# CRUVI-GT.net
KiCad netlist of a schematic drawn in Altium Designer
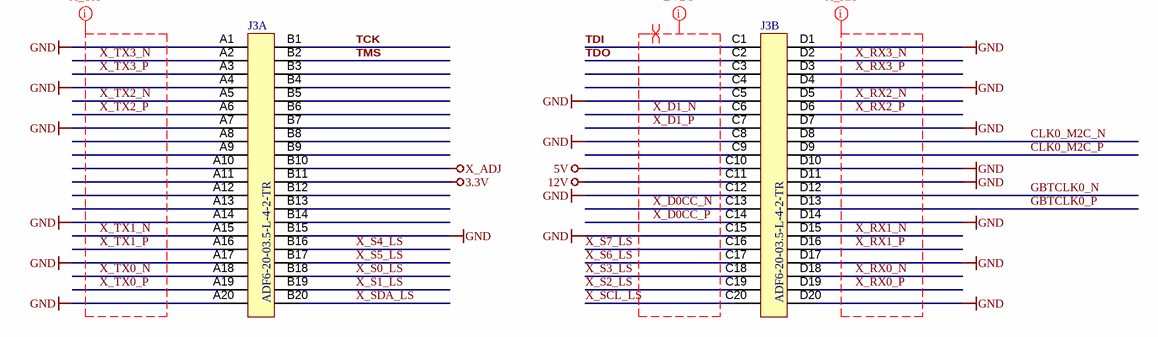
[diagram p0: CRUVI-GT.SchDoc]

(export (version "E")
  (design (tool "Eeschema 10.0.6"))
  (components
    (comp (ref "J3")
      (value "ADF6-20-03.5-L-4-2-TR")
      (footprint "ADF6-20-03.5-L-4-2")
      (fields (field (name "VOLTAGE") "155 VAC"))
      (libsource (lib "TE") (part "CON-20-A-D"))
    )
  )
  (nets
    (net (code "1") (name "/CLK0_M2C_N") (class "Default")
      (node (ref "J3") (pin "D8") (pinfunction "D8_D8") (pintype "passive"))
    )
    (net (code "2") (name "/CLK0_M2C_P") (class "Default")
      (node (ref "J3") (pin "D9") (pinfunction "D9_D9") (pintype "passive"))
    )
    (net (code "3") (name "/GBTCLK0_N") (class "Default")
      (node (ref "J3") (pin "D12") (pinfunction "D12_D12") (pintype "passive"))
    )
    (net (code "4") (name "/GBTCLK0_P") (class "Default")
      (node (ref "J3") (pin "D13") (pinfunction "D13_D13") (pintype "passive"))
    )
    (net (code "5") (name "/TCK") (class "Default")
      (node (ref "J3") (pin "B1") (pinfunction "B1_B1") (pintype "passive"))
    )
    (net (code "6") (name "/TDI") (class "Default")
      (node (ref "J3") (pin "C1") (pinfunction "C1_C1") (pintype "passive"))
    )
    (net (code "7") (name "/TDO") (class "Default")
      (node (ref "J3") (pin "C2") (pinfunction "C2_C2") (pintype "passive"))
    )
    (net (code "8") (name "/TMS") (class "Default")
      (node (ref "J3") (pin "B2") (pinfunction "B2_B2") (pintype "passive"))
    )
    (net (code "9") (name "/X_D0CC_N") (class "Default")
      (node (ref "J3") (pin "C13") (pinfunction "C13_C13") (pintype "passive"))
    )
    (net (code "10") (name "/X_D0CC_P") (class "Default")
      (node (ref "J3") (pin "C14") (pinfunction "C14_C14") (pintype "passive"))
    )
    (net (code "11") (name "/X_D1_N") (class "Default")
      (node (ref "J3") (pin "C6") (pinfunction "C6_C6") (pintype "passive"))
    )
    (net (code "12") (name "/X_D1_P") (class "Default")
      (node (ref "J3") (pin "C7") (pinfunction "C7_C7") (pintype "passive"))
    )
    (net (code "13") (name "/X_RX0_N") (class "Default")
      (node (ref "J3") (pin "D18") (pinfunction "D18_D18") (pintype "passive"))
    )
    (net (code "14") (name "/X_RX0_P") (class "Default")
      (node (ref "J3") (pin "D19") (pinfunction "D19_D19") (pintype "passive"))
    )
    (net (code "15") (name "/X_RX1_N") (class "Default")
      (node (ref "J3") (pin "D15") (pinfunction "D15_D15") (pintype "passive"))
    )
    (net (code "16") (name "/X_RX1_P") (class "Default")
      (node (ref "J3") (pin "D16") (pinfunction "D16_D16") (pintype "passive"))
    )
    (net (code "17") (name "/X_RX2_N") (class "Default")
      (node (ref "J3") (pin "D5") (pinfunction "D5_D5") (pintype "passive"))
    )
    (net (code "18") (name "/X_RX2_P") (class "Default")
      (node (ref "J3") (pin "D6") (pinfunction "D6_D6") (pintype "passive"))
    )
    (net (code "19") (name "/X_RX3_N") (class "Default")
      (node (ref "J3") (pin "D2") (pinfunction "D2_D2") (pintype "passive"))
    )
    (net (code "20") (name "/X_RX3_P") (class "Default")
      (node (ref "J3") (pin "D3") (pinfunction "D3_D3") (pintype "passive"))
    )
    (net (code "21") (name "/X_S0_LS") (class "Default")
      (node (ref "J3") (pin "B18") (pinfunction "B18_B18") (pintype "passive"))
    )
    (net (code "22") (name "/X_S1_LS") (class "Default")
      (node (ref "J3") (pin "B19") (pinfunction "B19_B19") (pintype "passive"))
    )
    (net (code "23") (name "/X_S2_LS") (class "Default")
      (node (ref "J3") (pin "C19") (pinfunction "C19_C19") (pintype "passive"))
    )
    (net (code "24") (name "/X_S3_LS") (class "Default")
      (node (ref "J3") (pin "C18") (pinfunction "C18_C18") (pintype "passive"))
    )
    (net (code "25") (name "/X_S4_LS") (class "Default")
      (node (ref "J3") (pin "B16") (pinfunction "B16_B16") (pintype "passive"))
    )
    (net (code "26") (name "/X_S5_LS") (class "Default")
      (node (ref "J3") (pin "B17") (pinfunction "B17_B17") (pintype "passive"))
    )
    (net (code "27") (name "/X_S6_LS") (class "Default")
      (node (ref "J3") (pin "C17") (pinfunction "C17_C17") (pintype "passive"))
    )
    (net (code "28") (name "/X_S7_LS") (class "Default")
      (node (ref "J3") (pin "C16") (pinfunction "C16_C16") (pintype "passive"))
    )
    (net (code "29") (name "/X_SCL_LS") (class "Default")
      (node (ref "J3") (pin "C20") (pinfunction "C20_C20") (pintype "passive"))
    )
    (net (code "30") (name "/X_SDA_LS") (class "Default")
      (node (ref "J3") (pin "B20") (pinfunction "B20_B20") (pintype "passive"))
    )
    (net (code "31") (name "/X_TX0_N") (class "Default")
      (node (ref "J3") (pin "A18") (pinfunction "A18_A18") (pintype "passive"))
    )
    (net (code "32") (name "/X_TX0_P") (class "Default")
      (node (ref "J3") (pin "A19") (pinfunction "A19_A19") (pintype "passive"))
    )
    (net (code "33") (name "/X_TX1_N") (class "Default")
      (node (ref "J3") (pin "A15") (pinfunction "A15_A15") (pintype "passive"))
    )
    (net (code "34") (name "/X_TX1_P") (class "Default")
      (node (ref "J3") (pin "A16") (pinfunction "A16_A16") (pintype "passive"))
    )
    (net (code "35") (name "/X_TX2_N") (class "Default")
      (node (ref "J3") (pin "A5") (pinfunction "A5_A5") (pintype "passive"))
    )
    (net (code "36") (name "/X_TX2_P") (class "Default")
      (node (ref "J3") (pin "A6") (pinfunction "A6_A6") (pintype "passive"))
    )
    (net (code "37") (name "/X_TX3_N") (class "Default")
      (node (ref "J3") (pin "A2") (pinfunction "A2_A2") (pintype "passive"))
    )
    (net (code "38") (name "/X_TX3_P") (class "Default")
      (node (ref "J3") (pin "A3") (pinfunction "A3_A3") (pintype "passive"))
    )
    (net (code "39") (name "3.3V") (class "Default")
      (node (ref "J3") (pin "B11") (pinfunction "B11_B11") (pintype "passive"))
    )
    (net (code "40") (name "5V") (class "Default")
      (node (ref "J3") (pin "C10") (pinfunction "C10_C10") (pintype "passive"))
    )
    (net (code "41") (name "12V") (class "Default")
      (node (ref "J3") (pin "C11") (pinfunction "C11_C11") (pintype "passive"))
    )
    (net (code "42") (name "GND") (class "Default")
      (node (ref "J3") (pin "A1") (pinfunction "A1_A1") (pintype "passive"))
      (node (ref "J3") (pin "A14") (pinfunction "A14_A14") (pintype "passive"))
      (node (ref "J3") (pin "A17") (pinfunction "A17_A17") (pintype "passive"))
      (node (ref "J3") (pin "A20") (pinfunction "A20_A20") (pintype "passive"))
      (node (ref "J3") (pin "A4") (pinfunction "A4_A4") (pintype "passive"))
      (node (ref "J3") (pin "A7") (pinfunction "A7_A7") (pintype "passive"))
      (node (ref "J3") (pin "B15") (pinfunction "B15_B15") (pintype "passive"))
      (node (ref "J3") (pin "C12") (pinfunction "C12_C12") (pintype "passive"))
      (node (ref "J3") (pin "C15") (pinfunction "C15_C15") (pintype "passive"))
      (node (ref "J3") (pin "C5") (pinfunction "C5_C5") (pintype "passive"))
      (node (ref "J3") (pin "C8") (pinfunction "C8_C8") (pintype "passive"))
      (node (ref "J3") (pin "D1") (pinfunction "D1_D1") (pintype "passive"))
      (node (ref "J3") (pin "D10") (pinfunction "D10_D10") (pintype "passive"))
      (node (ref "J3") (pin "D11") (pinfunction "D11_D11") (pintype "passive"))
      (node (ref "J3") (pin "D14") (pinfunction "D14_D14") (pintype "passive"))
      (node (ref "J3") (pin "D17") (pinfunction "D17_D17") (pintype "passive"))
      (node (ref "J3") (pin "D20") (pinfunction "D20_D20") (pintype "passive"))
      (node (ref "J3") (pin "D4") (pinfunction "D4_D4") (pintype "passive"))
      (node (ref "J3") (pin "D7") (pinfunction "D7_D7") (pintype "passive"))
    )
    (net (code "43") (name "X_ADJ") (class "Default")
      (node (ref "J3") (pin "B10") (pinfunction "B10_B10") (pintype "passive"))
    )
    (net (code "44") (name "unconnected-(J3-PadA8)") (class "Default")
      (node (ref "J3") (pin "A8") (pinfunction "A8_A8") (pintype "passive"))
    )
    (net (code "45") (name "unconnected-(J3-PadA9)") (class "Default")
      (node (ref "J3") (pin "A9") (pinfunction "A9_A9") (pintype "passive"))
    )
    (net (code "46") (name "unconnected-(J3-PadA10)") (class "Default")
      (node (ref "J3") (pin "A10") (pinfunction "A10_A10") (pintype "passive"))
    )
    (net (code "47") (name "unconnected-(J3-PadA11)") (class "Default")
      (node (ref "J3") (pin "A11") (pinfunction "A11_A11") (pintype "passive"))
    )
    (net (code "48") (name "unconnected-(J3-PadA12)") (class "Default")
      (node (ref "J3") (pin "A12") (pinfunction "A12_A12") (pintype "passive"))
    )
    (net (code "49") (name "unconnected-(J3-PadA13)") (class "Default")
      (node (ref "J3") (pin "A13") (pinfunction "A13_A13") (pintype "passive"))
    )
    (net (code "50") (name "unconnected-(J3-PadB3)") (class "Default")
      (node (ref "J3") (pin "B3") (pinfunction "B3_B3") (pintype "passive"))
    )
    (net (code "51") (name "unconnected-(J3-PadB4)") (class "Default")
      (node (ref "J3") (pin "B4") (pinfunction "B4_B4") (pintype "passive"))
    )
    (net (code "52") (name "unconnected-(J3-PadB5)") (class "Default")
      (node (ref "J3") (pin "B5") (pinfunction "B5_B5") (pintype "passive"))
    )
    (net (code "53") (name "unconnected-(J3-PadB6)") (class "Default")
      (node (ref "J3") (pin "B6") (pinfunction "B6_B6") (pintype "passive"))
    )
    (net (code "54") (name "unconnected-(J3-PadB7)") (class "Default")
      (node (ref "J3") (pin "B7") (pinfunction "B7_B7") (pintype "passive"))
    )
    (net (code "55") (name "unconnected-(J3-PadB8)") (class "Default")
      (node (ref "J3") (pin "B8") (pinfunction "B8_B8") (pintype "passive"))
    )
    (net (code "56") (name "unconnected-(J3-PadB9)") (class "Default")
      (node (ref "J3") (pin "B9") (pinfunction "B9_B9") (pintype "passive"))
    )
    (net (code "57") (name "unconnected-(J3-PadB12)") (class "Default")
      (node (ref "J3") (pin "B12") (pinfunction "B12_B12") (pintype "passive"))
    )
    (net (code "58") (name "unconnected-(J3-PadB13)") (class "Default")
      (node (ref "J3") (pin "B13") (pinfunction "B13_B13") (pintype "passive"))
    )
    (net (code "59") (name "unconnected-(J3-PadB14)") (class "Default")
      (node (ref "J3") (pin "B14") (pinfunction "B14_B14") (pintype "passive"))
    )
    (net (code "60") (name "unconnected-(J3-PadC3)") (class "Default")
      (node (ref "J3") (pin "C3") (pinfunction "C3_C3") (pintype "passive"))
    )
    (net (code "61") (name "unconnected-(J3-PadC4)") (class "Default")
      (node (ref "J3") (pin "C4") (pinfunction "C4_C4") (pintype "passive"))
    )
    (net (code "62") (name "unconnected-(J3-PadC9)") (class "Default")
      (node (ref "J3") (pin "C9") (pinfunction "C9_C9") (pintype "passive"))
    )
  )
)
